# B113A.net
KiCad netlist of a schematic drawn in EAGLE
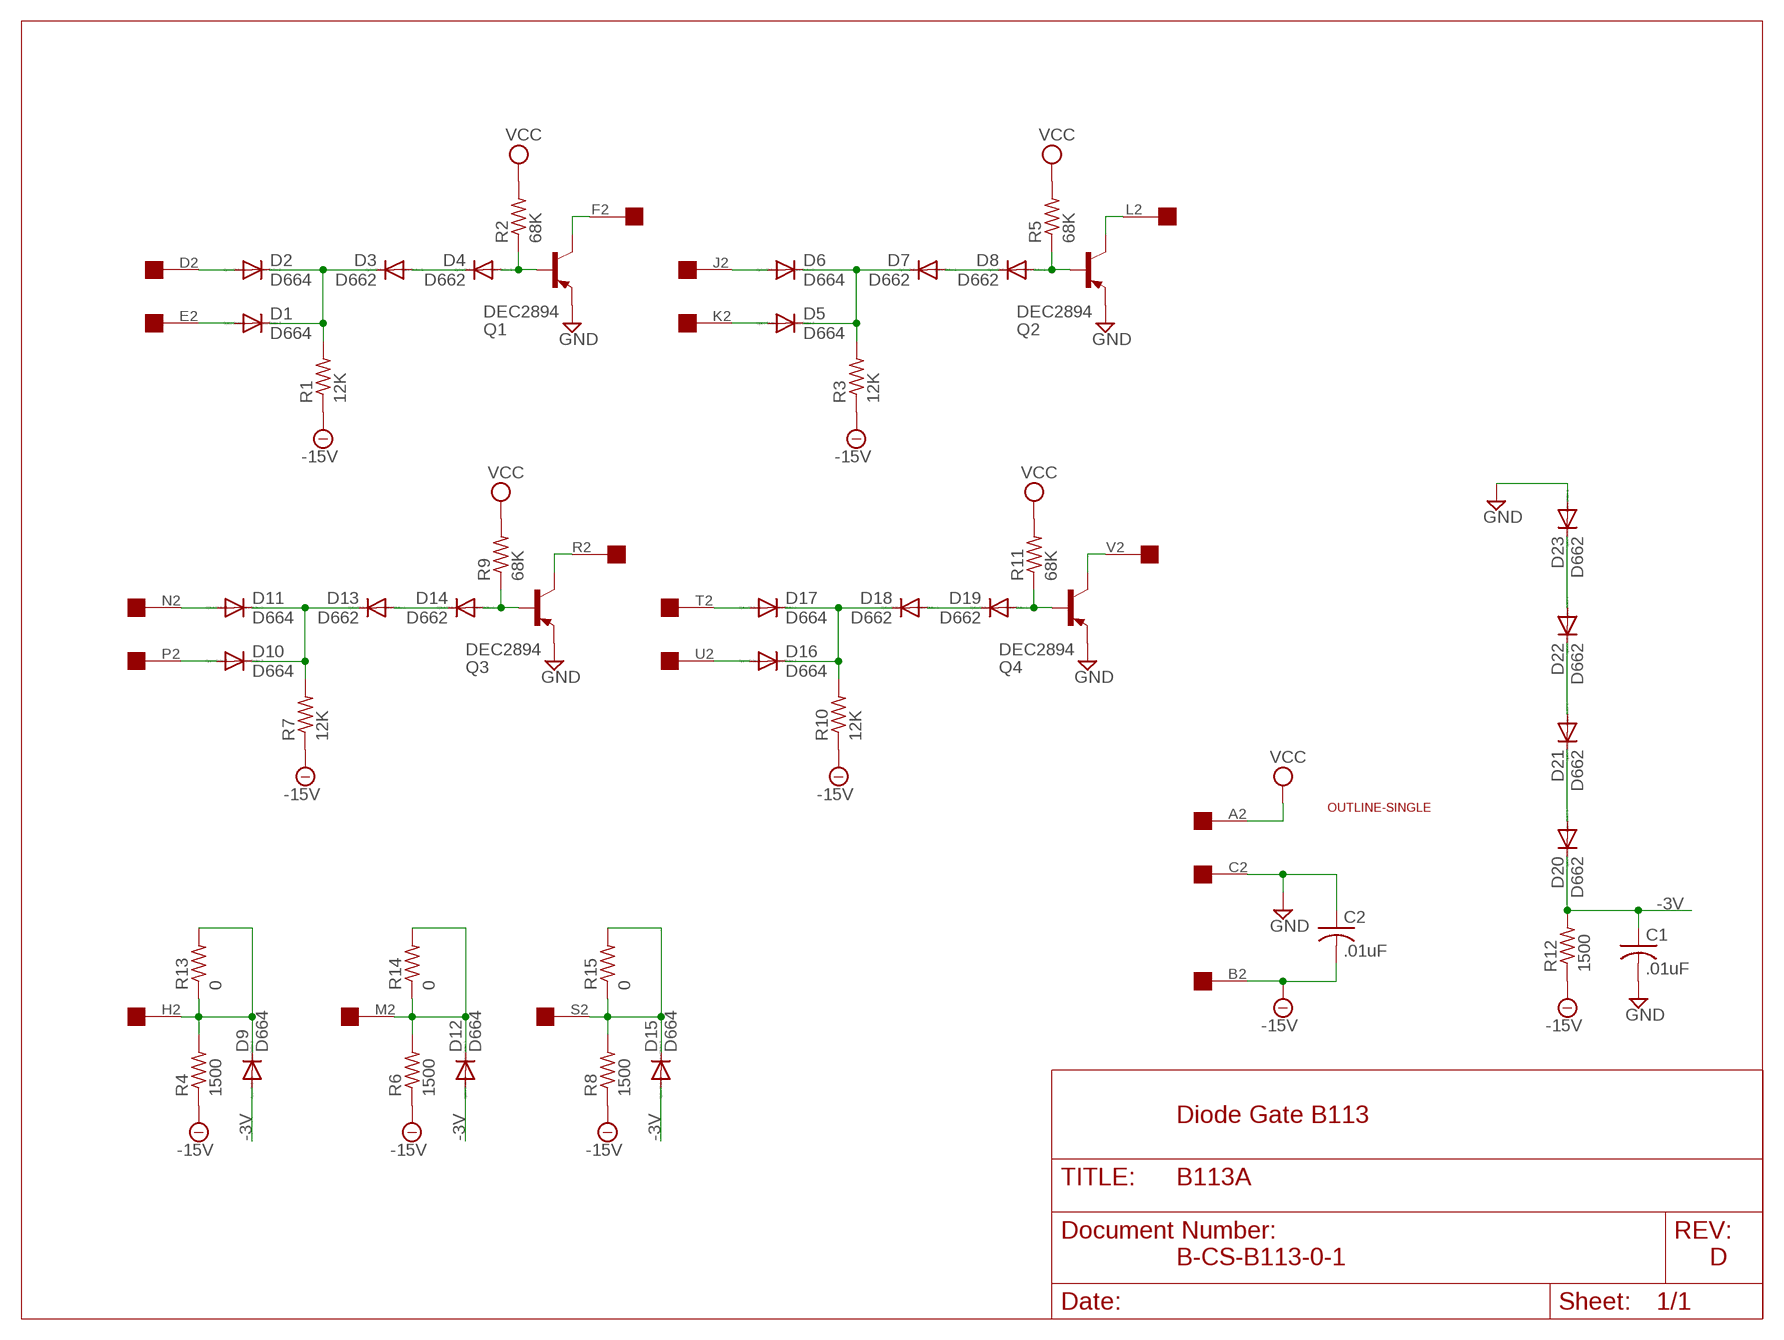
[diagram p0: schematic, sheet 1]

(export (version "E")
  (design (tool "Eeschema 10.0.6"))
  (components
    (comp (ref "C1")
      (value ".01uF")
      (footprint "eagle-import:C063-025X075")
      (libsource (lib "eagle-import") (part "C-US"))
    )
    (comp (ref "C2")
      (value ".01uF")
      (footprint "eagle-import:C063-025X075")
      (libsource (lib "eagle-import") (part "C-US"))
    )
    (comp (ref "D1")
      (value "D664")
      (footprint "eagle-import:DO35-10")
      (libsource (lib "eagle-import") (part "DIODE-DO35-10"))
    )
    (comp (ref "D2")
      (value "D664")
      (footprint "eagle-import:DO35-10")
      (libsource (lib "eagle-import") (part "DIODE-DO35-10"))
    )
    (comp (ref "D3")
      (value "D662")
      (footprint "eagle-import:DO35-10")
      (libsource (lib "eagle-import") (part "DIODE-DO35-10"))
    )
    (comp (ref "D4")
      (value "D662")
      (footprint "eagle-import:DO35-10")
      (libsource (lib "eagle-import") (part "DIODE-DO35-10"))
    )
    (comp (ref "D5")
      (value "D664")
      (footprint "eagle-import:DO35-10")
      (libsource (lib "eagle-import") (part "DIODE-DO35-10"))
    )
    (comp (ref "D6")
      (value "D664")
      (footprint "eagle-import:DO35-10")
      (libsource (lib "eagle-import") (part "DIODE-DO35-10"))
    )
    (comp (ref "D7")
      (value "D662")
      (footprint "eagle-import:DO35-10")
      (libsource (lib "eagle-import") (part "DIODE-DO35-10"))
    )
    (comp (ref "D8")
      (value "D662")
      (footprint "eagle-import:DO35-10")
      (libsource (lib "eagle-import") (part "DIODE-DO35-10"))
    )
    (comp (ref "D9")
      (value "D664")
      (footprint "eagle-import:DO35-10")
      (libsource (lib "eagle-import") (part "DIODE-DO35-10"))
    )
    (comp (ref "D10")
      (value "D664")
      (footprint "eagle-import:DO35-10")
      (libsource (lib "eagle-import") (part "DIODE-DO35-10"))
    )
    (comp (ref "D11")
      (value "D664")
      (footprint "eagle-import:DO35-10")
      (libsource (lib "eagle-import") (part "DIODE-DO35-10"))
    )
    (comp (ref "D12")
      (value "D664")
      (footprint "eagle-import:DO35-10")
      (libsource (lib "eagle-import") (part "DIODE-DO35-10"))
    )
    (comp (ref "D13")
      (value "D662")
      (footprint "eagle-import:DO35-10")
      (libsource (lib "eagle-import") (part "DIODE-DO35-10"))
    )
    (comp (ref "D14")
      (value "D662")
      (footprint "eagle-import:DO35-10")
      (libsource (lib "eagle-import") (part "DIODE-DO35-10"))
    )
    (comp (ref "D15")
      (value "D664")
      (footprint "eagle-import:DO35-10")
      (libsource (lib "eagle-import") (part "DIODE-DO35-10"))
    )
    (comp (ref "D16")
      (value "D664")
      (footprint "eagle-import:DO35-10")
      (libsource (lib "eagle-import") (part "DIODE-DO35-10"))
    )
    (comp (ref "D17")
      (value "D664")
      (footprint "eagle-import:DO35-10")
      (libsource (lib "eagle-import") (part "DIODE-DO35-10"))
    )
    (comp (ref "D18")
      (value "D662")
      (footprint "eagle-import:DO35-10")
      (libsource (lib "eagle-import") (part "DIODE-DO35-10"))
    )
    (comp (ref "D19")
      (value "D662")
      (footprint "eagle-import:DO35-10")
      (libsource (lib "eagle-import") (part "DIODE-DO35-10"))
    )
    (comp (ref "D20")
      (value "D662")
      (footprint "eagle-import:DO35-10")
      (libsource (lib "eagle-import") (part "DIODE-DO35-10"))
    )
    (comp (ref "D21")
      (value "D662")
      (footprint "eagle-import:DO35-10")
      (libsource (lib "eagle-import") (part "DIODE-DO35-10"))
    )
    (comp (ref "D22")
      (value "D662")
      (footprint "eagle-import:DO35-10")
      (libsource (lib "eagle-import") (part "DIODE-DO35-10"))
    )
    (comp (ref "D23")
      (value "D662")
      (footprint "eagle-import:DO35-10")
      (libsource (lib "eagle-import") (part "DIODE-DO35-10"))
    )
    (comp (ref "Q1")
      (value "DEC2894")
      (footprint "eagle-import:TO5")
      (libsource (lib "eagle-import") (part "-PNP-TO5"))
    )
    (comp (ref "Q2")
      (value "DEC2894")
      (footprint "eagle-import:TO5")
      (libsource (lib "eagle-import") (part "-PNP-TO5"))
    )
    (comp (ref "Q3")
      (value "DEC2894")
      (footprint "eagle-import:TO5")
      (libsource (lib "eagle-import") (part "-PNP-TO5"))
    )
    (comp (ref "Q4")
      (value "DEC2894")
      (footprint "eagle-import:TO5")
      (libsource (lib "eagle-import") (part "-PNP-TO5"))
    )
    (comp (ref "R1")
      (value "12K")
      (footprint "eagle-import:0207_10")
      (libsource (lib "eagle-import") (part "R-US_0207/10"))
    )
    (comp (ref "R2")
      (value "68K")
      (footprint "eagle-import:0207_10")
      (libsource (lib "eagle-import") (part "R-US_0207/10"))
    )
    (comp (ref "R3")
      (value "12K")
      (footprint "eagle-import:0207_10")
      (libsource (lib "eagle-import") (part "R-US_0207/10"))
    )
    (comp (ref "R4")
      (value "1500")
      (footprint "eagle-import:0207_10")
      (libsource (lib "eagle-import") (part "R-US_0207/10"))
    )
    (comp (ref "R5")
      (value "68K")
      (footprint "eagle-import:0207_10")
      (libsource (lib "eagle-import") (part "R-US_0207/10"))
    )
    (comp (ref "R6")
      (value "1500")
      (footprint "eagle-import:0207_10")
      (libsource (lib "eagle-import") (part "R-US_0207/10"))
    )
    (comp (ref "R7")
      (value "12K")
      (footprint "eagle-import:0207_10")
      (libsource (lib "eagle-import") (part "R-US_0207/10"))
    )
    (comp (ref "R8")
      (value "1500")
      (footprint "eagle-import:0207_10")
      (libsource (lib "eagle-import") (part "R-US_0207/10"))
    )
    (comp (ref "R9")
      (value "68K")
      (footprint "eagle-import:0207_10")
      (libsource (lib "eagle-import") (part "R-US_0207/10"))
    )
    (comp (ref "R10")
      (value "12K")
      (footprint "eagle-import:0207_10")
      (libsource (lib "eagle-import") (part "R-US_0207/10"))
    )
    (comp (ref "R11")
      (value "68K")
      (footprint "eagle-import:0207_10")
      (libsource (lib "eagle-import") (part "R-US_0207/10"))
    )
    (comp (ref "R12")
      (value "1500")
      (footprint "eagle-import:0207_10")
      (libsource (lib "eagle-import") (part "R-US_0207/10"))
    )
    (comp (ref "R13")
      (value "0")
      (footprint "eagle-import:0207_10")
      (libsource (lib "eagle-import") (part "R-US_0207/10"))
    )
    (comp (ref "R14")
      (value "0")
      (footprint "eagle-import:0207_10")
      (libsource (lib "eagle-import") (part "R-US_0207/10"))
    )
    (comp (ref "R15")
      (value "0")
      (footprint "eagle-import:0207_10")
      (libsource (lib "eagle-import") (part "R-US_0207/10"))
    )
    (comp (ref "U$1")
      (value "OUTLINE-SINGLE")
      (footprint "eagle-import:SINGLE")
      (libsource (lib "eagle-import") (part "OUTLINE-SINGLE"))
    )
    (comp (ref "U$2")
      (value "EDGE-1")
      (footprint "eagle-import:EDGE-CON1")
      (libsource (lib "eagle-import") (part "EDGE-1"))
    )
  )
  (nets
    (net (code "1") (name "-15V") (class "Default")
      (node (ref "C2") (pin "2") (pinfunction "2_2") (pintype "passive"))
      (node (ref "R1") (pin "1") (pinfunction "1_1") (pintype "passive"))
      (node (ref "R10") (pin "1") (pinfunction "1_1") (pintype "passive"))
      (node (ref "R12") (pin "1") (pinfunction "1_1") (pintype "passive"))
      (node (ref "R3") (pin "1") (pinfunction "1_1") (pintype "passive"))
      (node (ref "R4") (pin "1") (pinfunction "1_1") (pintype "passive"))
      (node (ref "R6") (pin "1") (pinfunction "1_1") (pintype "passive"))
      (node (ref "R7") (pin "1") (pinfunction "1_1") (pintype "passive"))
      (node (ref "R8") (pin "1") (pinfunction "1_1") (pintype "passive"))
      (node (ref "U$2") (pin "B2") (pinfunction "1_B2") (pintype "bidirectional"))
    )
    (net (code "2") (name "/-3V") (class "Default")
      (node (ref "C1") (pin "1") (pinfunction "1_1") (pintype "passive"))
      (node (ref "D12") (pin "A") (pinfunction "A_A") (pintype "passive"))
      (node (ref "D15") (pin "A") (pinfunction "A_A") (pintype "passive"))
      (node (ref "D20") (pin "C") (pinfunction "C_C") (pintype "passive"))
      (node (ref "D9") (pin "A") (pinfunction "A_A") (pintype "passive"))
      (node (ref "R12") (pin "2") (pinfunction "2_2") (pintype "passive"))
    )
    (net (code "3") (name "GND") (class "Default")
      (node (ref "C1") (pin "2") (pinfunction "2_2") (pintype "passive"))
      (node (ref "C2") (pin "1") (pinfunction "1_1") (pintype "passive"))
      (node (ref "D23") (pin "A") (pinfunction "A_A") (pintype "passive"))
      (node (ref "Q1") (pin "1") (pinfunction "E_1") (pintype "passive"))
      (node (ref "Q2") (pin "1") (pinfunction "E_1") (pintype "passive"))
      (node (ref "Q3") (pin "1") (pinfunction "E_1") (pintype "passive"))
      (node (ref "Q4") (pin "1") (pinfunction "E_1") (pintype "passive"))
      (node (ref "U$2") (pin "C2") (pinfunction "1_C2") (pintype "bidirectional"))
    )
    (net (code "4") (name "Net-(D1-PadC)") (class "Default")
      (node (ref "D1") (pin "C") (pinfunction "C_C") (pintype "passive"))
      (node (ref "D2") (pin "C") (pinfunction "C_C") (pintype "passive"))
      (node (ref "D3") (pin "C") (pinfunction "C_C") (pintype "passive"))
      (node (ref "R1") (pin "2") (pinfunction "2_2") (pintype "passive"))
    )
    (net (code "5") (name "Net-(D3-PadA)") (class "Default")
      (node (ref "D3") (pin "A") (pinfunction "A_A") (pintype "passive"))
      (node (ref "D4") (pin "C") (pinfunction "C_C") (pintype "passive"))
    )
    (net (code "6") (name "Net-(D5-PadC)") (class "Default")
      (node (ref "D5") (pin "C") (pinfunction "C_C") (pintype "passive"))
      (node (ref "D6") (pin "C") (pinfunction "C_C") (pintype "passive"))
      (node (ref "D7") (pin "C") (pinfunction "C_C") (pintype "passive"))
      (node (ref "R3") (pin "2") (pinfunction "2_2") (pintype "passive"))
    )
    (net (code "7") (name "Net-(D7-PadA)") (class "Default")
      (node (ref "D7") (pin "A") (pinfunction "A_A") (pintype "passive"))
      (node (ref "D8") (pin "C") (pinfunction "C_C") (pintype "passive"))
    )
    (net (code "8") (name "Net-(D10-PadC)") (class "Default")
      (node (ref "D10") (pin "C") (pinfunction "C_C") (pintype "passive"))
      (node (ref "D11") (pin "C") (pinfunction "C_C") (pintype "passive"))
      (node (ref "D13") (pin "C") (pinfunction "C_C") (pintype "passive"))
      (node (ref "R7") (pin "2") (pinfunction "2_2") (pintype "passive"))
    )
    (net (code "9") (name "Net-(D13-PadA)") (class "Default")
      (node (ref "D13") (pin "A") (pinfunction "A_A") (pintype "passive"))
      (node (ref "D14") (pin "C") (pinfunction "C_C") (pintype "passive"))
    )
    (net (code "10") (name "Net-(D16-PadC)") (class "Default")
      (node (ref "D16") (pin "C") (pinfunction "C_C") (pintype "passive"))
      (node (ref "D17") (pin "C") (pinfunction "C_C") (pintype "passive"))
      (node (ref "D18") (pin "C") (pinfunction "C_C") (pintype "passive"))
      (node (ref "R10") (pin "2") (pinfunction "2_2") (pintype "passive"))
    )
    (net (code "11") (name "Net-(D18-PadA)") (class "Default")
      (node (ref "D18") (pin "A") (pinfunction "A_A") (pintype "passive"))
      (node (ref "D19") (pin "C") (pinfunction "C_C") (pintype "passive"))
    )
    (net (code "12") (name "Net-(D20-PadA)") (class "Default")
      (node (ref "D20") (pin "A") (pinfunction "A_A") (pintype "passive"))
      (node (ref "D21") (pin "C") (pinfunction "C_C") (pintype "passive"))
    )
    (net (code "13") (name "Net-(D21-PadA)") (class "Default")
      (node (ref "D21") (pin "A") (pinfunction "A_A") (pintype "passive"))
      (node (ref "D22") (pin "C") (pinfunction "C_C") (pintype "passive"))
    )
    (net (code "14") (name "Net-(D22-PadA)") (class "Default")
      (node (ref "D22") (pin "A") (pinfunction "A_A") (pintype "passive"))
      (node (ref "D23") (pin "C") (pinfunction "C_C") (pintype "passive"))
    )
    (net (code "15") (name "Net-(Q1-B)") (class "Default")
      (node (ref "D4") (pin "A") (pinfunction "A_A") (pintype "passive"))
      (node (ref "Q1") (pin "2") (pinfunction "B_2") (pintype "passive"))
      (node (ref "R2") (pin "1") (pinfunction "1_1") (pintype "passive"))
    )
    (net (code "16") (name "Net-(Q1-C)") (class "Default")
      (node (ref "Q1") (pin "3") (pinfunction "C_3") (pintype "passive"))
      (node (ref "U$2") (pin "F2") (pinfunction "1_F2") (pintype "bidirectional"))
    )
    (net (code "17") (name "Net-(Q2-B)") (class "Default")
      (node (ref "D8") (pin "A") (pinfunction "A_A") (pintype "passive"))
      (node (ref "Q2") (pin "2") (pinfunction "B_2") (pintype "passive"))
      (node (ref "R5") (pin "1") (pinfunction "1_1") (pintype "passive"))
    )
    (net (code "18") (name "Net-(Q2-C)") (class "Default")
      (node (ref "Q2") (pin "3") (pinfunction "C_3") (pintype "passive"))
      (node (ref "U$2") (pin "L2") (pinfunction "1_L2") (pintype "bidirectional"))
    )
    (net (code "19") (name "Net-(Q3-B)") (class "Default")
      (node (ref "D14") (pin "A") (pinfunction "A_A") (pintype "passive"))
      (node (ref "Q3") (pin "2") (pinfunction "B_2") (pintype "passive"))
      (node (ref "R9") (pin "1") (pinfunction "1_1") (pintype "passive"))
    )
    (net (code "20") (name "Net-(Q3-C)") (class "Default")
      (node (ref "Q3") (pin "3") (pinfunction "C_3") (pintype "passive"))
      (node (ref "U$2") (pin "R2") (pinfunction "1_R2") (pintype "bidirectional"))
    )
    (net (code "21") (name "Net-(Q4-B)") (class "Default")
      (node (ref "D19") (pin "A") (pinfunction "A_A") (pintype "passive"))
      (node (ref "Q4") (pin "2") (pinfunction "B_2") (pintype "passive"))
      (node (ref "R11") (pin "1") (pinfunction "1_1") (pintype "passive"))
    )
    (net (code "22") (name "Net-(Q4-C)") (class "Default")
      (node (ref "Q4") (pin "3") (pinfunction "C_3") (pintype "passive"))
      (node (ref "U$2") (pin "V2") (pinfunction "1_V2") (pintype "bidirectional"))
    )
    (net (code "23") (name "Net-(U$2D-1)") (class "Default")
      (node (ref "D2") (pin "A") (pinfunction "A_A") (pintype "passive"))
      (node (ref "U$2") (pin "D2") (pinfunction "1_D2") (pintype "bidirectional"))
    )
    (net (code "24") (name "Net-(U$2E-1)") (class "Default")
      (node (ref "D1") (pin "A") (pinfunction "A_A") (pintype "passive"))
      (node (ref "U$2") (pin "E2") (pinfunction "1_E2") (pintype "bidirectional"))
    )
    (net (code "25") (name "Net-(U$2G-1)") (class "Default")
      (node (ref "D9") (pin "C") (pinfunction "C_C") (pintype "passive"))
      (node (ref "R13") (pin "1") (pinfunction "1_1") (pintype "passive"))
      (node (ref "R13") (pin "2") (pinfunction "2_2") (pintype "passive"))
      (node (ref "R4") (pin "2") (pinfunction "2_2") (pintype "passive"))
      (node (ref "U$2") (pin "H2") (pinfunction "1_H2") (pintype "bidirectional"))
    )
    (net (code "26") (name "Net-(U$2H-1)") (class "Default")
      (node (ref "D6") (pin "A") (pinfunction "A_A") (pintype "passive"))
      (node (ref "U$2") (pin "J2") (pinfunction "1_J2") (pintype "bidirectional"))
    )
    (net (code "27") (name "Net-(U$2I-1)") (class "Default")
      (node (ref "D5") (pin "A") (pinfunction "A_A") (pintype "passive"))
      (node (ref "U$2") (pin "K2") (pinfunction "1_K2") (pintype "bidirectional"))
    )
    (net (code "28") (name "Net-(U$2K-1)") (class "Default")
      (node (ref "D12") (pin "C") (pinfunction "C_C") (pintype "passive"))
      (node (ref "R14") (pin "1") (pinfunction "1_1") (pintype "passive"))
      (node (ref "R14") (pin "2") (pinfunction "2_2") (pintype "passive"))
      (node (ref "R6") (pin "2") (pinfunction "2_2") (pintype "passive"))
      (node (ref "U$2") (pin "M2") (pinfunction "1_M2") (pintype "bidirectional"))
    )
    (net (code "29") (name "Net-(U$2L-1)") (class "Default")
      (node (ref "D11") (pin "A") (pinfunction "A_A") (pintype "passive"))
      (node (ref "U$2") (pin "N2") (pinfunction "1_N2") (pintype "bidirectional"))
    )
    (net (code "30") (name "Net-(U$2M-1)") (class "Default")
      (node (ref "D10") (pin "A") (pinfunction "A_A") (pintype "passive"))
      (node (ref "U$2") (pin "P2") (pinfunction "1_P2") (pintype "bidirectional"))
    )
    (net (code "31") (name "Net-(U$2O-1)") (class "Default")
      (node (ref "D15") (pin "C") (pinfunction "C_C") (pintype "passive"))
      (node (ref "R15") (pin "1") (pinfunction "1_1") (pintype "passive"))
      (node (ref "R15") (pin "2") (pinfunction "2_2") (pintype "passive"))
      (node (ref "R8") (pin "2") (pinfunction "2_2") (pintype "passive"))
      (node (ref "U$2") (pin "S2") (pinfunction "1_S2") (pintype "bidirectional"))
    )
    (net (code "32") (name "Net-(U$2P-1)") (class "Default")
      (node (ref "D17") (pin "A") (pinfunction "A_A") (pintype "passive"))
      (node (ref "U$2") (pin "T2") (pinfunction "1_T2") (pintype "bidirectional"))
    )
    (net (code "33") (name "Net-(U$2Q-1)") (class "Default")
      (node (ref "D16") (pin "A") (pinfunction "A_A") (pintype "passive"))
      (node (ref "U$2") (pin "U2") (pinfunction "1_U2") (pintype "bidirectional"))
    )
    (net (code "34") (name "VCC") (class "Default")
      (node (ref "R11") (pin "2") (pinfunction "2_2") (pintype "passive"))
      (node (ref "R2") (pin "2") (pinfunction "2_2") (pintype "passive"))
      (node (ref "R5") (pin "2") (pinfunction "2_2") (pintype "passive"))
      (node (ref "R9") (pin "2") (pinfunction "2_2") (pintype "passive"))
      (node (ref "U$2") (pin "A2") (pinfunction "1_A2") (pintype "bidirectional"))
    )
  )
)
